# R151A.net
KiCad netlist of a schematic drawn in EAGLE
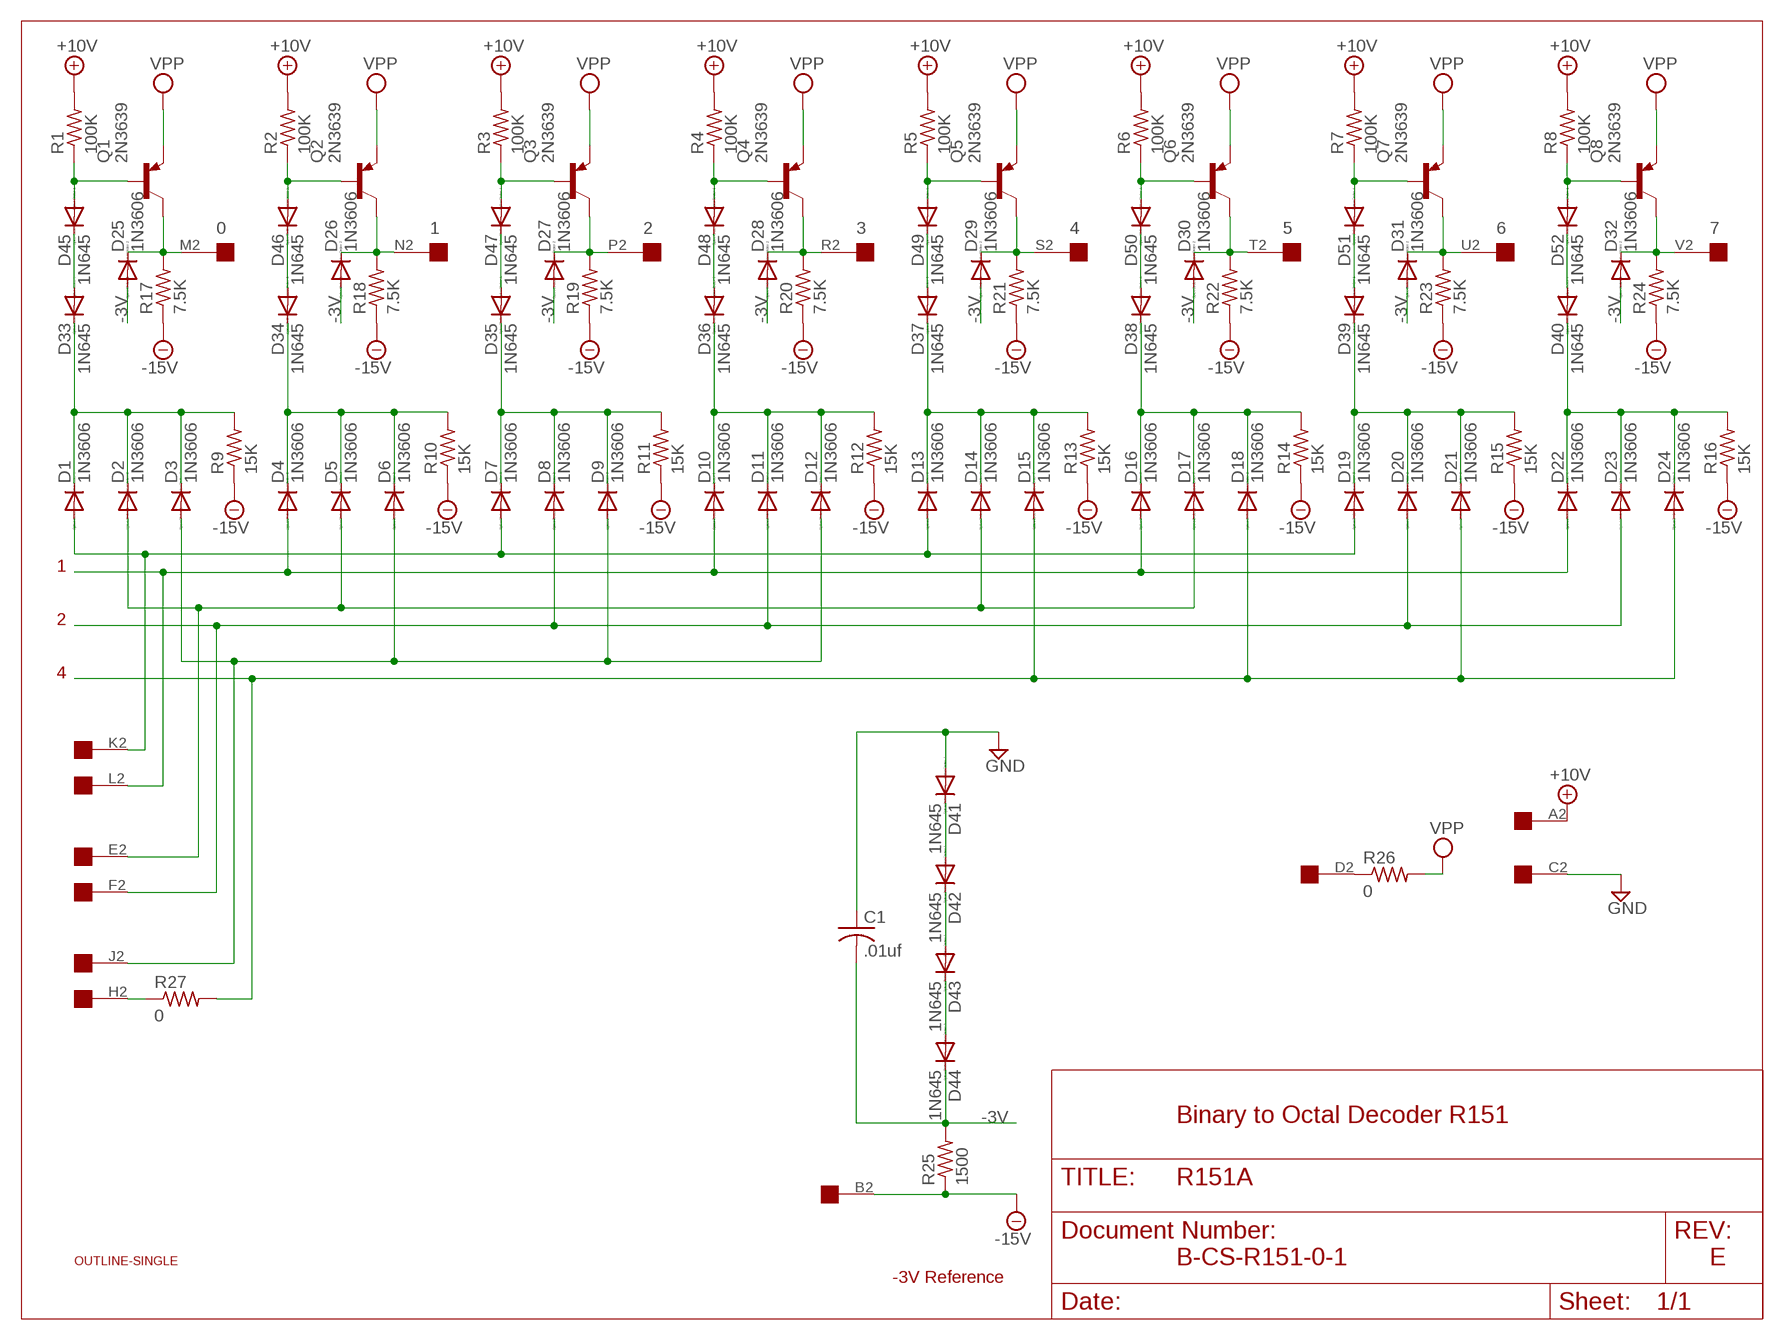
[diagram p0: schematic, sheet 1]

(export (version "E")
  (design (tool "Eeschema 10.0.6"))
  (components
    (comp (ref "C1")
      (value ".01uf")
      (footprint "eagle-import:C050-025X075")
      (libsource (lib "eagle-import") (part "C-US050-025X075"))
    )
    (comp (ref "D1")
      (value "1N3606")
      (footprint "eagle-import:DO35-10")
      (libsource (lib "eagle-import") (part "1N4148DO35-10"))
    )
    (comp (ref "D2")
      (value "1N3606")
      (footprint "eagle-import:DO35-10")
      (libsource (lib "eagle-import") (part "1N4148DO35-10"))
    )
    (comp (ref "D3")
      (value "1N3606")
      (footprint "eagle-import:DO35-10")
      (libsource (lib "eagle-import") (part "1N4148DO35-10"))
    )
    (comp (ref "D4")
      (value "1N3606")
      (footprint "eagle-import:DO35-10")
      (libsource (lib "eagle-import") (part "1N4148DO35-10"))
    )
    (comp (ref "D5")
      (value "1N3606")
      (footprint "eagle-import:DO35-10")
      (libsource (lib "eagle-import") (part "1N4148DO35-10"))
    )
    (comp (ref "D6")
      (value "1N3606")
      (footprint "eagle-import:DO35-10")
      (libsource (lib "eagle-import") (part "1N4148DO35-10"))
    )
    (comp (ref "D7")
      (value "1N3606")
      (footprint "eagle-import:DO35-10")
      (libsource (lib "eagle-import") (part "1N4148DO35-10"))
    )
    (comp (ref "D8")
      (value "1N3606")
      (footprint "eagle-import:DO35-10")
      (libsource (lib "eagle-import") (part "1N4148DO35-10"))
    )
    (comp (ref "D9")
      (value "1N3606")
      (footprint "eagle-import:DO35-10")
      (libsource (lib "eagle-import") (part "1N4148DO35-10"))
    )
    (comp (ref "D10")
      (value "1N3606")
      (footprint "eagle-import:DO35-10")
      (libsource (lib "eagle-import") (part "1N4148DO35-10"))
    )
    (comp (ref "D11")
      (value "1N3606")
      (footprint "eagle-import:DO35-10")
      (libsource (lib "eagle-import") (part "1N4148DO35-10"))
    )
    (comp (ref "D12")
      (value "1N3606")
      (footprint "eagle-import:DO35-10")
      (libsource (lib "eagle-import") (part "1N4148DO35-10"))
    )
    (comp (ref "D13")
      (value "1N3606")
      (footprint "eagle-import:DO35-10")
      (libsource (lib "eagle-import") (part "1N4148DO35-10"))
    )
    (comp (ref "D14")
      (value "1N3606")
      (footprint "eagle-import:DO35-10")
      (libsource (lib "eagle-import") (part "1N4148DO35-10"))
    )
    (comp (ref "D15")
      (value "1N3606")
      (footprint "eagle-import:DO35-10")
      (libsource (lib "eagle-import") (part "1N4148DO35-10"))
    )
    (comp (ref "D16")
      (value "1N3606")
      (footprint "eagle-import:DO35-10")
      (libsource (lib "eagle-import") (part "1N4148DO35-10"))
    )
    (comp (ref "D17")
      (value "1N3606")
      (footprint "eagle-import:DO35-10")
      (libsource (lib "eagle-import") (part "1N4148DO35-10"))
    )
    (comp (ref "D18")
      (value "1N3606")
      (footprint "eagle-import:DO35-10")
      (libsource (lib "eagle-import") (part "1N4148DO35-10"))
    )
    (comp (ref "D19")
      (value "1N3606")
      (footprint "eagle-import:DO35-10")
      (libsource (lib "eagle-import") (part "1N4148DO35-10"))
    )
    (comp (ref "D20")
      (value "1N3606")
      (footprint "eagle-import:DO35-10")
      (libsource (lib "eagle-import") (part "1N4148DO35-10"))
    )
    (comp (ref "D21")
      (value "1N3606")
      (footprint "eagle-import:DO35-10")
      (libsource (lib "eagle-import") (part "1N4148DO35-10"))
    )
    (comp (ref "D22")
      (value "1N3606")
      (footprint "eagle-import:DO35-10")
      (libsource (lib "eagle-import") (part "1N4148DO35-10"))
    )
    (comp (ref "D23")
      (value "1N3606")
      (footprint "eagle-import:DO35-10")
      (libsource (lib "eagle-import") (part "1N4148DO35-10"))
    )
    (comp (ref "D24")
      (value "1N3606")
      (footprint "eagle-import:DO35-10")
      (libsource (lib "eagle-import") (part "1N4148DO35-10"))
    )
    (comp (ref "D25")
      (value "1N3606")
      (footprint "eagle-import:DO35-10")
      (libsource (lib "eagle-import") (part "1N4148DO35-10"))
    )
    (comp (ref "D26")
      (value "1N3606")
      (footprint "eagle-import:DO35-10")
      (libsource (lib "eagle-import") (part "1N4148DO35-10"))
    )
    (comp (ref "D27")
      (value "1N3606")
      (footprint "eagle-import:DO35-10")
      (libsource (lib "eagle-import") (part "1N4148DO35-10"))
    )
    (comp (ref "D28")
      (value "1N3606")
      (footprint "eagle-import:DO35-10")
      (libsource (lib "eagle-import") (part "1N4148DO35-10"))
    )
    (comp (ref "D29")
      (value "1N3606")
      (footprint "eagle-import:DO35-10")
      (libsource (lib "eagle-import") (part "1N4148DO35-10"))
    )
    (comp (ref "D30")
      (value "1N3606")
      (footprint "eagle-import:DO35-10")
      (libsource (lib "eagle-import") (part "1N4148DO35-10"))
    )
    (comp (ref "D31")
      (value "1N3606")
      (footprint "eagle-import:DO35-10")
      (libsource (lib "eagle-import") (part "1N4148DO35-10"))
    )
    (comp (ref "D32")
      (value "1N3606")
      (footprint "eagle-import:DO35-10")
      (libsource (lib "eagle-import") (part "1N4148DO35-10"))
    )
    (comp (ref "D33")
      (value "1N645")
      (footprint "eagle-import:DO35-10")
      (libsource (lib "eagle-import") (part "1N4148DO35-10"))
    )
    (comp (ref "D34")
      (value "1N645")
      (footprint "eagle-import:DO35-10")
      (libsource (lib "eagle-import") (part "1N4148DO35-10"))
    )
    (comp (ref "D35")
      (value "1N645")
      (footprint "eagle-import:DO35-10")
      (libsource (lib "eagle-import") (part "1N4148DO35-10"))
    )
    (comp (ref "D36")
      (value "1N645")
      (footprint "eagle-import:DO35-10")
      (libsource (lib "eagle-import") (part "1N4148DO35-10"))
    )
    (comp (ref "D37")
      (value "1N645")
      (footprint "eagle-import:DO35-10")
      (libsource (lib "eagle-import") (part "1N4148DO35-10"))
    )
    (comp (ref "D38")
      (value "1N645")
      (footprint "eagle-import:DO35-10")
      (libsource (lib "eagle-import") (part "1N4148DO35-10"))
    )
    (comp (ref "D39")
      (value "1N645")
      (footprint "eagle-import:DO35-10")
      (libsource (lib "eagle-import") (part "1N4148DO35-10"))
    )
    (comp (ref "D40")
      (value "1N645")
      (footprint "eagle-import:DO35-10")
      (libsource (lib "eagle-import") (part "1N4148DO35-10"))
    )
    (comp (ref "D41")
      (value "1N645")
      (footprint "eagle-import:DO35-10")
      (libsource (lib "eagle-import") (part "1N4148DO35-10"))
    )
    (comp (ref "D42")
      (value "1N645")
      (footprint "eagle-import:DO35-10")
      (libsource (lib "eagle-import") (part "1N4148DO35-10"))
    )
    (comp (ref "D43")
      (value "1N645")
      (footprint "eagle-import:DO35-10")
      (libsource (lib "eagle-import") (part "1N4148DO35-10"))
    )
    (comp (ref "D44")
      (value "1N645")
      (footprint "eagle-import:DO35-10")
      (libsource (lib "eagle-import") (part "1N4148DO35-10"))
    )
    (comp (ref "D45")
      (value "1N645")
      (footprint "eagle-import:DO35-10")
      (libsource (lib "eagle-import") (part "1N4148DO35-10"))
    )
    (comp (ref "D46")
      (value "1N645")
      (footprint "eagle-import:DO35-10")
      (libsource (lib "eagle-import") (part "1N4148DO35-10"))
    )
    (comp (ref "D47")
      (value "1N645")
      (footprint "eagle-import:DO35-10")
      (libsource (lib "eagle-import") (part "1N4148DO35-10"))
    )
    (comp (ref "D48")
      (value "1N645")
      (footprint "eagle-import:DO35-10")
      (libsource (lib "eagle-import") (part "1N4148DO35-10"))
    )
    (comp (ref "D49")
      (value "1N645")
      (footprint "eagle-import:DO35-10")
      (libsource (lib "eagle-import") (part "1N4148DO35-10"))
    )
    (comp (ref "D50")
      (value "1N645")
      (footprint "eagle-import:DO35-10")
      (libsource (lib "eagle-import") (part "1N4148DO35-10"))
    )
    (comp (ref "D51")
      (value "1N645")
      (footprint "eagle-import:DO35-10")
      (libsource (lib "eagle-import") (part "1N4148DO35-10"))
    )
    (comp (ref "D52")
      (value "1N645")
      (footprint "eagle-import:DO35-10")
      (libsource (lib "eagle-import") (part "1N4148DO35-10"))
    )
    (comp (ref "Q1")
      (value "2N3639")
      (footprint "eagle-import:TO39")
      (libsource (lib "eagle-import") (part "2N3637"))
    )
    (comp (ref "Q2")
      (value "2N3639")
      (footprint "eagle-import:TO39")
      (libsource (lib "eagle-import") (part "2N3637"))
    )
    (comp (ref "Q3")
      (value "2N3639")
      (footprint "eagle-import:TO39")
      (libsource (lib "eagle-import") (part "2N3637"))
    )
    (comp (ref "Q4")
      (value "2N3639")
      (footprint "eagle-import:TO39")
      (libsource (lib "eagle-import") (part "2N3637"))
    )
    (comp (ref "Q5")
      (value "2N3639")
      (footprint "eagle-import:TO39")
      (libsource (lib "eagle-import") (part "2N3637"))
    )
    (comp (ref "Q6")
      (value "2N3639")
      (footprint "eagle-import:TO39")
      (libsource (lib "eagle-import") (part "2N3637"))
    )
    (comp (ref "Q7")
      (value "2N3639")
      (footprint "eagle-import:TO39")
      (libsource (lib "eagle-import") (part "2N3637"))
    )
    (comp (ref "Q8")
      (value "2N3639")
      (footprint "eagle-import:TO39")
      (libsource (lib "eagle-import") (part "2N3637"))
    )
    (comp (ref "R1")
      (value "100K")
      (footprint "eagle-import:0207_10")
      (libsource (lib "eagle-import") (part "R-US_0207/10"))
    )
    (comp (ref "R2")
      (value "100K")
      (footprint "eagle-import:0207_10")
      (libsource (lib "eagle-import") (part "R-US_0207/10"))
    )
    (comp (ref "R3")
      (value "100K")
      (footprint "eagle-import:0207_10")
      (libsource (lib "eagle-import") (part "R-US_0207/10"))
    )
    (comp (ref "R4")
      (value "100K")
      (footprint "eagle-import:0207_10")
      (libsource (lib "eagle-import") (part "R-US_0207/10"))
    )
    (comp (ref "R5")
      (value "100K")
      (footprint "eagle-import:0207_10")
      (libsource (lib "eagle-import") (part "R-US_0207/10"))
    )
    (comp (ref "R6")
      (value "100K")
      (footprint "eagle-import:0207_10")
      (libsource (lib "eagle-import") (part "R-US_0207/10"))
    )
    (comp (ref "R7")
      (value "100K")
      (footprint "eagle-import:0207_10")
      (libsource (lib "eagle-import") (part "R-US_0207/10"))
    )
    (comp (ref "R8")
      (value "100K")
      (footprint "eagle-import:0207_10")
      (libsource (lib "eagle-import") (part "R-US_0207/10"))
    )
    (comp (ref "R9")
      (value "15K")
      (footprint "eagle-import:0207_10")
      (libsource (lib "eagle-import") (part "R-US_0207/10"))
    )
    (comp (ref "R10")
      (value "15K")
      (footprint "eagle-import:0207_10")
      (libsource (lib "eagle-import") (part "R-US_0207/10"))
    )
    (comp (ref "R11")
      (value "15K")
      (footprint "eagle-import:0207_10")
      (libsource (lib "eagle-import") (part "R-US_0207/10"))
    )
    (comp (ref "R12")
      (value "15K")
      (footprint "eagle-import:0207_10")
      (libsource (lib "eagle-import") (part "R-US_0207/10"))
    )
    (comp (ref "R13")
      (value "15K")
      (footprint "eagle-import:0207_10")
      (libsource (lib "eagle-import") (part "R-US_0207/10"))
    )
    (comp (ref "R14")
      (value "15K")
      (footprint "eagle-import:0207_10")
      (libsource (lib "eagle-import") (part "R-US_0207/10"))
    )
    (comp (ref "R15")
      (value "15K")
      (footprint "eagle-import:0207_10")
      (libsource (lib "eagle-import") (part "R-US_0207/10"))
    )
    (comp (ref "R16")
      (value "15K")
      (footprint "eagle-import:0207_10")
      (libsource (lib "eagle-import") (part "R-US_0207/10"))
    )
    (comp (ref "R17")
      (value "7.5K")
      (footprint "eagle-import:0207_10")
      (libsource (lib "eagle-import") (part "R-US_0207/10"))
    )
    (comp (ref "R18")
      (value "7.5K")
      (footprint "eagle-import:0207_10")
      (libsource (lib "eagle-import") (part "R-US_0207/10"))
    )
    (comp (ref "R19")
      (value "7.5K")
      (footprint "eagle-import:0207_10")
      (libsource (lib "eagle-import") (part "R-US_0207/10"))
    )
    (comp (ref "R20")
      (value "7.5K")
      (footprint "eagle-import:0207_10")
      (libsource (lib "eagle-import") (part "R-US_0207/10"))
    )
    (comp (ref "R21")
      (value "7.5K")
      (footprint "eagle-import:0207_10")
      (libsource (lib "eagle-import") (part "R-US_0207/10"))
    )
    (comp (ref "R22")
      (value "7.5K")
      (footprint "eagle-import:0207_10")
      (libsource (lib "eagle-import") (part "R-US_0207/10"))
    )
    (comp (ref "R23")
      (value "7.5K")
      (footprint "eagle-import:0207_10")
      (libsource (lib "eagle-import") (part "R-US_0207/10"))
    )
    (comp (ref "R24")
      (value "7.5K")
      (footprint "eagle-import:0207_10")
      (libsource (lib "eagle-import") (part "R-US_0207/10"))
    )
    (comp (ref "R25")
      (value "1500")
      (footprint "eagle-import:0207_10")
      (libsource (lib "eagle-import") (part "R-US_0207/10"))
    )
    (comp (ref "R26")
      (value "0")
      (footprint "eagle-import:0207_10")
      (libsource (lib "eagle-import") (part "R-US_0207/10"))
    )
    (comp (ref "R27")
      (value "0")
      (footprint "eagle-import:0207_10")
      (libsource (lib "eagle-import") (part "R-US_0207/10"))
    )
    (comp (ref "U$1")
      (value "OUTLINE-SINGLE")
      (footprint "eagle-import:SINGLE")
      (libsource (lib "eagle-import") (part "OUTLINE-SINGLE"))
    )
    (comp (ref "U$2")
      (value "EDGE-1")
      (footprint "eagle-import:EDGE-CON1")
      (libsource (lib "eagle-import") (part "EDGE-1"))
    )
  )
  (nets
    (net (code "1") (name "+10V") (class "Default")
      (node (ref "R1") (pin "2") (pinfunction "2_2") (pintype "passive"))
      (node (ref "R2") (pin "2") (pinfunction "2_2") (pintype "passive"))
      (node (ref "R3") (pin "2") (pinfunction "2_2") (pintype "passive"))
      (node (ref "R4") (pin "2") (pinfunction "2_2") (pintype "passive"))
      (node (ref "R5") (pin "2") (pinfunction "2_2") (pintype "passive"))
      (node (ref "R6") (pin "2") (pinfunction "2_2") (pintype "passive"))
      (node (ref "R7") (pin "2") (pinfunction "2_2") (pintype "passive"))
      (node (ref "R8") (pin "2") (pinfunction "2_2") (pintype "passive"))
      (node (ref "U$2") (pin "A2") (pinfunction "1_A2") (pintype "bidirectional"))
    )
    (net (code "2") (name "-15V") (class "Default")
      (node (ref "R10") (pin "1") (pinfunction "1_1") (pintype "passive"))
      (node (ref "R11") (pin "1") (pinfunction "1_1") (pintype "passive"))
      (node (ref "R12") (pin "1") (pinfunction "1_1") (pintype "passive"))
      (node (ref "R13") (pin "1") (pinfunction "1_1") (pintype "passive"))
      (node (ref "R14") (pin "1") (pinfunction "1_1") (pintype "passive"))
      (node (ref "R15") (pin "1") (pinfunction "1_1") (pintype "passive"))
      (node (ref "R16") (pin "1") (pinfunction "1_1") (pintype "passive"))
      (node (ref "R17") (pin "1") (pinfunction "1_1") (pintype "passive"))
      (node (ref "R18") (pin "1") (pinfunction "1_1") (pintype "passive"))
      (node (ref "R19") (pin "1") (pinfunction "1_1") (pintype "passive"))
      (node (ref "R20") (pin "1") (pinfunction "1_1") (pintype "passive"))
      (node (ref "R21") (pin "1") (pinfunction "1_1") (pintype "passive"))
      (node (ref "R22") (pin "1") (pinfunction "1_1") (pintype "passive"))
      (node (ref "R23") (pin "1") (pinfunction "1_1") (pintype "passive"))
      (node (ref "R24") (pin "1") (pinfunction "1_1") (pintype "passive"))
      (node (ref "R25") (pin "1") (pinfunction "1_1") (pintype "passive"))
      (node (ref "R9") (pin "1") (pinfunction "1_1") (pintype "passive"))
      (node (ref "U$2") (pin "B2") (pinfunction "1_B2") (pintype "bidirectional"))
    )
    (net (code "3") (name "/-3V") (class "Default")
      (node (ref "C1") (pin "2") (pinfunction "2_2") (pintype "passive"))
      (node (ref "D25") (pin "A") (pinfunction "A_A") (pintype "passive"))
      (node (ref "D26") (pin "A") (pinfunction "A_A") (pintype "passive"))
      (node (ref "D27") (pin "A") (pinfunction "A_A") (pintype "passive"))
      (node (ref "D28") (pin "A") (pinfunction "A_A") (pintype "passive"))
      (node (ref "D29") (pin "A") (pinfunction "A_A") (pintype "passive"))
      (node (ref "D30") (pin "A") (pinfunction "A_A") (pintype "passive"))
      (node (ref "D31") (pin "A") (pinfunction "A_A") (pintype "passive"))
      (node (ref "D32") (pin "A") (pinfunction "A_A") (pintype "passive"))
      (node (ref "D44") (pin "C") (pinfunction "C_C") (pintype "passive"))
      (node (ref "R25") (pin "2") (pinfunction "2_2") (pintype "passive"))
    )
    (net (code "4") (name "/0") (class "Default")
      (node (ref "D25") (pin "C") (pinfunction "C_C") (pintype "passive"))
      (node (ref "Q1") (pin "3") (pinfunction "C_3") (pintype "passive"))
      (node (ref "R17") (pin "2") (pinfunction "2_2") (pintype "passive"))
      (node (ref "U$2") (pin "M2") (pinfunction "1_M2") (pintype "bidirectional"))
    )
    (net (code "5") (name "/1") (class "Default")
      (node (ref "D26") (pin "C") (pinfunction "C_C") (pintype "passive"))
      (node (ref "Q2") (pin "3") (pinfunction "C_3") (pintype "passive"))
      (node (ref "R18") (pin "2") (pinfunction "2_2") (pintype "passive"))
      (node (ref "U$2") (pin "N2") (pinfunction "1_N2") (pintype "bidirectional"))
    )
    (net (code "6") (name "/2") (class "Default")
      (node (ref "D27") (pin "C") (pinfunction "C_C") (pintype "passive"))
      (node (ref "Q3") (pin "3") (pinfunction "C_3") (pintype "passive"))
      (node (ref "R19") (pin "2") (pinfunction "2_2") (pintype "passive"))
      (node (ref "U$2") (pin "P2") (pinfunction "1_P2") (pintype "bidirectional"))
    )
    (net (code "7") (name "/3") (class "Default")
      (node (ref "D28") (pin "C") (pinfunction "C_C") (pintype "passive"))
      (node (ref "Q4") (pin "3") (pinfunction "C_3") (pintype "passive"))
      (node (ref "R20") (pin "2") (pinfunction "2_2") (pintype "passive"))
      (node (ref "U$2") (pin "R2") (pinfunction "1_R2") (pintype "bidirectional"))
    )
    (net (code "8") (name "/4") (class "Default")
      (node (ref "D29") (pin "C") (pinfunction "C_C") (pintype "passive"))
      (node (ref "Q5") (pin "3") (pinfunction "C_3") (pintype "passive"))
      (node (ref "R21") (pin "2") (pinfunction "2_2") (pintype "passive"))
      (node (ref "U$2") (pin "S2") (pinfunction "1_S2") (pintype "bidirectional"))
    )
    (net (code "9") (name "/5") (class "Default")
      (node (ref "D30") (pin "C") (pinfunction "C_C") (pintype "passive"))
      (node (ref "Q6") (pin "3") (pinfunction "C_3") (pintype "passive"))
      (node (ref "R22") (pin "2") (pinfunction "2_2") (pintype "passive"))
      (node (ref "U$2") (pin "T2") (pinfunction "1_T2") (pintype "bidirectional"))
    )
    (net (code "10") (name "/6") (class "Default")
      (node (ref "D31") (pin "C") (pinfunction "C_C") (pintype "passive"))
      (node (ref "Q7") (pin "3") (pinfunction "C_3") (pintype "passive"))
      (node (ref "R23") (pin "2") (pinfunction "2_2") (pintype "passive"))
      (node (ref "U$2") (pin "U2") (pinfunction "1_U2") (pintype "bidirectional"))
    )
    (net (code "11") (name "/7") (class "Default")
      (node (ref "D32") (pin "C") (pinfunction "C_C") (pintype "passive"))
      (node (ref "Q8") (pin "3") (pinfunction "C_3") (pintype "passive"))
      (node (ref "R24") (pin "2") (pinfunction "2_2") (pintype "passive"))
      (node (ref "U$2") (pin "V2") (pinfunction "1_V2") (pintype "bidirectional"))
    )
    (net (code "12") (name "GND") (class "Default")
      (node (ref "C1") (pin "1") (pinfunction "1_1") (pintype "passive"))
      (node (ref "D41") (pin "A") (pinfunction "A_A") (pintype "passive"))
      (node (ref "U$2") (pin "C2") (pinfunction "1_C2") (pintype "bidirectional"))
    )
    (net (code "13") (name "Net-(D1-PadC)") (class "Default")
      (node (ref "D1") (pin "C") (pinfunction "C_C") (pintype "passive"))
      (node (ref "D2") (pin "C") (pinfunction "C_C") (pintype "passive"))
      (node (ref "D3") (pin "C") (pinfunction "C_C") (pintype "passive"))
      (node (ref "D33") (pin "C") (pinfunction "C_C") (pintype "passive"))
      (node (ref "R9") (pin "2") (pinfunction "2_2") (pintype "passive"))
    )
    (net (code "14") (name "Net-(D10-PadC)") (class "Default")
      (node (ref "D10") (pin "C") (pinfunction "C_C") (pintype "passive"))
      (node (ref "D11") (pin "C") (pinfunction "C_C") (pintype "passive"))
      (node (ref "D12") (pin "C") (pinfunction "C_C") (pintype "passive"))
      (node (ref "D36") (pin "C") (pinfunction "C_C") (pintype "passive"))
      (node (ref "R12") (pin "2") (pinfunction "2_2") (pintype "passive"))
    )
    (net (code "15") (name "Net-(D13-PadC)") (class "Default")
      (node (ref "D13") (pin "C") (pinfunction "C_C") (pintype "passive"))
      (node (ref "D14") (pin "C") (pinfunction "C_C") (pintype "passive"))
      (node (ref "D15") (pin "C") (pinfunction "C_C") (pintype "passive"))
      (node (ref "D37") (pin "C") (pinfunction "C_C") (pintype "passive"))
      (node (ref "R13") (pin "2") (pinfunction "2_2") (pintype "passive"))
    )
    (net (code "16") (name "Net-(D15-PadA)") (class "Default")
      (node (ref "D15") (pin "A") (pinfunction "A_A") (pintype "passive"))
      (node (ref "D18") (pin "A") (pinfunction "A_A") (pintype "passive"))
      (node (ref "D21") (pin "A") (pinfunction "A_A") (pintype "passive"))
      (node (ref "D24") (pin "A") (pinfunction "A_A") (pintype "passive"))
      (node (ref "R27") (pin "2") (pinfunction "2_2") (pintype "passive"))
    )
    (net (code "17") (name "Net-(D16-PadC)") (class "Default")
      (node (ref "D16") (pin "C") (pinfunction "C_C") (pintype "passive"))
      (node (ref "D17") (pin "C") (pinfunction "C_C") (pintype "passive"))
      (node (ref "D18") (pin "C") (pinfunction "C_C") (pintype "passive"))
      (node (ref "D38") (pin "C") (pinfunction "C_C") (pintype "passive"))
      (node (ref "R14") (pin "2") (pinfunction "2_2") (pintype "passive"))
    )
    (net (code "18") (name "Net-(D19-PadC)") (class "Default")
      (node (ref "D19") (pin "C") (pinfunction "C_C") (pintype "passive"))
      (node (ref "D20") (pin "C") (pinfunction "C_C") (pintype "passive"))
      (node (ref "D21") (pin "C") (pinfunction "C_C") (pintype "passive"))
      (node (ref "D39") (pin "C") (pinfunction "C_C") (pintype "passive"))
      (node (ref "R15") (pin "2") (pinfunction "2_2") (pintype "passive"))
    )
    (net (code "19") (name "Net-(D22-PadC)") (class "Default")
      (node (ref "D22") (pin "C") (pinfunction "C_C") (pintype "passive"))
      (node (ref "D23") (pin "C") (pinfunction "C_C") (pintype "passive"))
      (node (ref "D24") (pin "C") (pinfunction "C_C") (pintype "passive"))
      (node (ref "D40") (pin "C") (pinfunction "C_C") (pintype "passive"))
      (node (ref "R16") (pin "2") (pinfunction "2_2") (pintype "passive"))
    )
    (net (code "20") (name "Net-(D33-PadA)") (class "Default")
      (node (ref "D33") (pin "A") (pinfunction "A_A") (pintype "passive"))
      (node (ref "D45") (pin "C") (pinfunction "C_C") (pintype "passive"))
    )
    (net (code "21") (name "Net-(D34-PadA)") (class "Default")
      (node (ref "D34") (pin "A") (pinfunction "A_A") (pintype "passive"))
      (node (ref "D46") (pin "C") (pinfunction "C_C") (pintype "passive"))
    )
    (net (code "22") (name "Net-(D34-PadC)") (class "Default")
      (node (ref "D34") (pin "C") (pinfunction "C_C") (pintype "passive"))
      (node (ref "D4") (pin "C") (pinfunction "C_C") (pintype "passive"))
      (node (ref "D5") (pin "C") (pinfunction "C_C") (pintype "passive"))
      (node (ref "D6") (pin "C") (pinfunction "C_C") (pintype "passive"))
      (node (ref "R10") (pin "2") (pinfunction "2_2") (pintype "passive"))
    )
    (net (code "23") (name "Net-(D35-PadA)") (class "Default")
      (node (ref "D35") (pin "A") (pinfunction "A_A") (pintype "passive"))
      (node (ref "D47") (pin "C") (pinfunction "C_C") (pintype "passive"))
    )
    (net (code "24") (name "Net-(D35-PadC)") (class "Default")
      (node (ref "D35") (pin "C") (pinfunction "C_C") (pintype "passive"))
      (node (ref "D7") (pin "C") (pinfunction "C_C") (pintype "passive"))
      (node (ref "D8") (pin "C") (pinfunction "C_C") (pintype "passive"))
      (node (ref "D9") (pin "C") (pinfunction "C_C") (pintype "passive"))
      (node (ref "R11") (pin "2") (pinfunction "2_2") (pintype "passive"))
    )
    (net (code "25") (name "Net-(D36-PadA)") (class "Default")
      (node (ref "D36") (pin "A") (pinfunction "A_A") (pintype "passive"))
      (node (ref "D48") (pin "C") (pinfunction "C_C") (pintype "passive"))
    )
    (net (code "26") (name "Net-(D37-PadA)") (class "Default")
      (node (ref "D37") (pin "A") (pinfunction "A_A") (pintype "passive"))
      (node (ref "D49") (pin "C") (pinfunction "C_C") (pintype "passive"))
    )
    (net (code "27") (name "Net-(D38-PadA)") (class "Default")
      (node (ref "D38") (pin "A") (pinfunction "A_A") (pintype "passive"))
      (node (ref "D50") (pin "C") (pinfunction "C_C") (pintype "passive"))
    )
    (net (code "28") (name "Net-(D39-PadA)") (class "Default")
      (node (ref "D39") (pin "A") (pinfunction "A_A") (pintype "passive"))
      (node (ref "D51") (pin "C") (pinfunction "C_C") (pintype "passive"))
    )
    (net (code "29") (name "Net-(D40-PadA)") (class "Default")
      (node (ref "D40") (pin "A") (pinfunction "A_A") (pintype "passive"))
      (node (ref "D52") (pin "C") (pinfunction "C_C") (pintype "passive"))
    )
    (net (code "30") (name "Net-(D41-PadC)") (class "Default")
      (node (ref "D41") (pin "C") (pinfunction "C_C") (pintype "passive"))
      (node (ref "D42") (pin "A") (pinfunction "A_A") (pintype "passive"))
    )
    (net (code "31") (name "Net-(D42-PadC)") (class "Default")
      (node (ref "D42") (pin "C") (pinfunction "C_C") (pintype "passive"))
      (node (ref "D43") (pin "A") (pinfunction "A_A") (pintype "passive"))
    )
    (net (code "32") (name "Net-(D43-PadC)") (class "Default")
      (node (ref "D43") (pin "C") (pinfunction "C_C") (pintype "passive"))
      (node (ref "D44") (pin "A") (pinfunction "A_A") (pintype "passive"))
    )
    (net (code "33") (name "Net-(Q1-B)") (class "Default")
      (node (ref "D45") (pin "A") (pinfunction "A_A") (pintype "passive"))
      (node (ref "Q1") (pin "2") (pinfunction "B_2") (pintype "passive"))
      (node (ref "R1") (pin "1") (pinfunction "1_1") (pintype "passive"))
    )
    (net (code "34") (name "Net-(Q2-B)") (class "Default")
      (node (ref "D46") (pin "A") (pinfunction "A_A") (pintype "passive"))
      (node (ref "Q2") (pin "2") (pinfunction "B_2") (pintype "passive"))
      (node (ref "R2") (pin "1") (pinfunction "1_1") (pintype "passive"))
    )
    (net (code "35") (name "Net-(Q3-B)") (class "Default")
      (node (ref "D47") (pin "A") (pinfunction "A_A") (pintype "passive"))
      (node (ref "Q3") (pin "2") (pinfunction "B_2") (pintype "passive"))
      (node (ref "R3") (pin "1") (pinfunction "1_1") (pintype "passive"))
    )
    (net (code "36") (name "Net-(Q4-B)") (class "Default")
      (node (ref "D48") (pin "A") (pinfunction "A_A") (pintype "passive"))
      (node (ref "Q4") (pin "2") (pinfunction "B_2") (pintype "passive"))
      (node (ref "R4") (pin "1") (pinfunction "1_1") (pintype "passive"))
    )
    (net (code "37") (name "Net-(Q5-B)") (class "Default")
      (node (ref "D49") (pin "A") (pinfunction "A_A") (pintype "passive"))
      (node (ref "Q5") (pin "2") (pinfunction "B_2") (pintype "passive"))
      (node (ref "R5") (pin "1") (pinfunction "1_1") (pintype "passive"))
    )
    (net (code "38") (name "Net-(Q6-B)") (class "Default")
      (node (ref "D50") (pin "A") (pinfunction "A_A") (pintype "passive"))
      (node (ref "Q6") (pin "2") (pinfunction "B_2") (pintype "passive"))
      (node (ref "R6") (pin "1") (pinfunction "1_1") (pintype "passive"))
    )
    (net (code "39") (name "Net-(Q7-B)") (class "Default")
      (node (ref "D51") (pin "A") (pinfunction "A_A") (pintype "passive"))
      (node (ref "Q7") (pin "2") (pinfunction "B_2") (pintype "passive"))
      (node (ref "R7") (pin "1") (pinfunction "1_1") (pintype "passive"))
    )
    (net (code "40") (name "Net-(Q8-B)") (class "Default")
      (node (ref "D52") (pin "A") (pinfunction "A_A") (pintype "passive"))
      (node (ref "Q8") (pin "2") (pinfunction "B_2") (pintype "passive"))
      (node (ref "R8") (pin "1") (pinfunction "1_1") (pintype "passive"))
    )
    (net (code "41") (name "Net-(U$2D-1)") (class "Default")
      (node (ref "R26") (pin "1") (pinfunction "1_1") (pintype "passive"))
      (node (ref "U$2") (pin "D2") (pinfunction "1_D2") (pintype "bidirectional"))
    )
    (net (code "42") (name "Net-(U$2E-1)") (class "Default")
      (node (ref "D14") (pin "A") (pinfunction "A_A") (pintype "passive"))
      (node (ref "D17") (pin "A") (pinfunction "A_A") (pintype "passive"))
      (node (ref "D2") (pin "A") (pinfunction "A_A") (pintype "passive"))
      (node (ref "D5") (pin "A") (pinfunction "A_A") (pintype "passive"))
      (node (ref "U$2") (pin "E2") (pinfunction "1_E2") (pintype "bidirectional"))
    )
    (net (code "43") (name "Net-(U$2F-1)") (class "Default")
      (node (ref "D11") (pin "A") (pinfunction "A_A") (pintype "passive"))
      (node (ref "D20") (pin "A") (pinfunction "A_A") (pintype "passive"))
      (node (ref "D23") (pin "A") (pinfunction "A_A") (pintype "passive"))
      (node (ref "D8") (pin "A") (pinfunction "A_A") (pintype "passive"))
      (node (ref "U$2") (pin "F2") (pinfunction "1_F2") (pintype "bidirectional"))
    )
    (net (code "44") (name "Net-(U$2G-1)") (class "Default")
      (node (ref "R27") (pin "1") (pinfunction "1_1") (pintype "passive"))
      (node (ref "U$2") (pin "H2") (pinfunction "1_H2") (pintype "bidirectional"))
    )
    (net (code "45") (name "Net-(U$2H-1)") (class "Default")
      (node (ref "D12") (pin "A") (pinfunction "A_A") (pintype "passive"))
      (node (ref "D3") (pin "A") (pinfunction "A_A") (pintype "passive"))
      (node (ref "D6") (pin "A") (pinfunction "A_A") (pintype "passive"))
      (node (ref "D9") (pin "A") (pinfunction "A_A") (pintype "passive"))
      (node (ref "U$2") (pin "J2") (pinfunction "1_J2") (pintype "bidirectional"))
    )
    (net (code "46") (name "Net-(U$2I-1)") (class "Default")
      (node (ref "D1") (pin "A") (pinfunction "A_A") (pintype "passive"))
      (node (ref "D13") (pin "A") (pinfunction "A_A") (pintype "passive"))
      (node (ref "D19") (pin "A") (pinfunction "A_A") (pintype "passive"))
      (node (ref "D7") (pin "A") (pinfunction "A_A") (pintype "passive"))
      (node (ref "U$2") (pin "K2") (pinfunction "1_K2") (pintype "bidirectional"))
    )
    (net (code "47") (name "Net-(U$2J-1)") (class "Default")
      (node (ref "D10") (pin "A") (pinfunction "A_A") (pintype "passive"))
      (node (ref "D16") (pin "A") (pinfunction "A_A") (pintype "passive"))
      (node (ref "D22") (pin "A") (pinfunction "A_A") (pintype "passive"))
      (node (ref "D4") (pin "A") (pinfunction "A_A") (pintype "passive"))
      (node (ref "U$2") (pin "L2") (pinfunction "1_L2") (pintype "bidirectional"))
    )
    (net (code "48") (name "VPP") (class "Default")
      (node (ref "Q1") (pin "1") (pinfunction "E_1") (pintype "passive"))
      (node (ref "Q2") (pin "1") (pinfunction "E_1") (pintype "passive"))
      (node (ref "Q3") (pin "1") (pinfunction "E_1") (pintype "passive"))
      (node (ref "Q4") (pin "1") (pinfunction "E_1") (pintype "passive"))
      (node (ref "Q5") (pin "1") (pinfunction "E_1") (pintype "passive"))
      (node (ref "Q6") (pin "1") (pinfunction "E_1") (pintype "passive"))
      (node (ref "Q7") (pin "1") (pinfunction "E_1") (pintype "passive"))
      (node (ref "Q8") (pin "1") (pinfunction "E_1") (pintype "passive"))
      (node (ref "R26") (pin "2") (pinfunction "2_2") (pintype "passive"))
    )
  )
)
